# digitalLatchShieldSMD.net
KiCad netlist of a schematic drawn in EAGLE
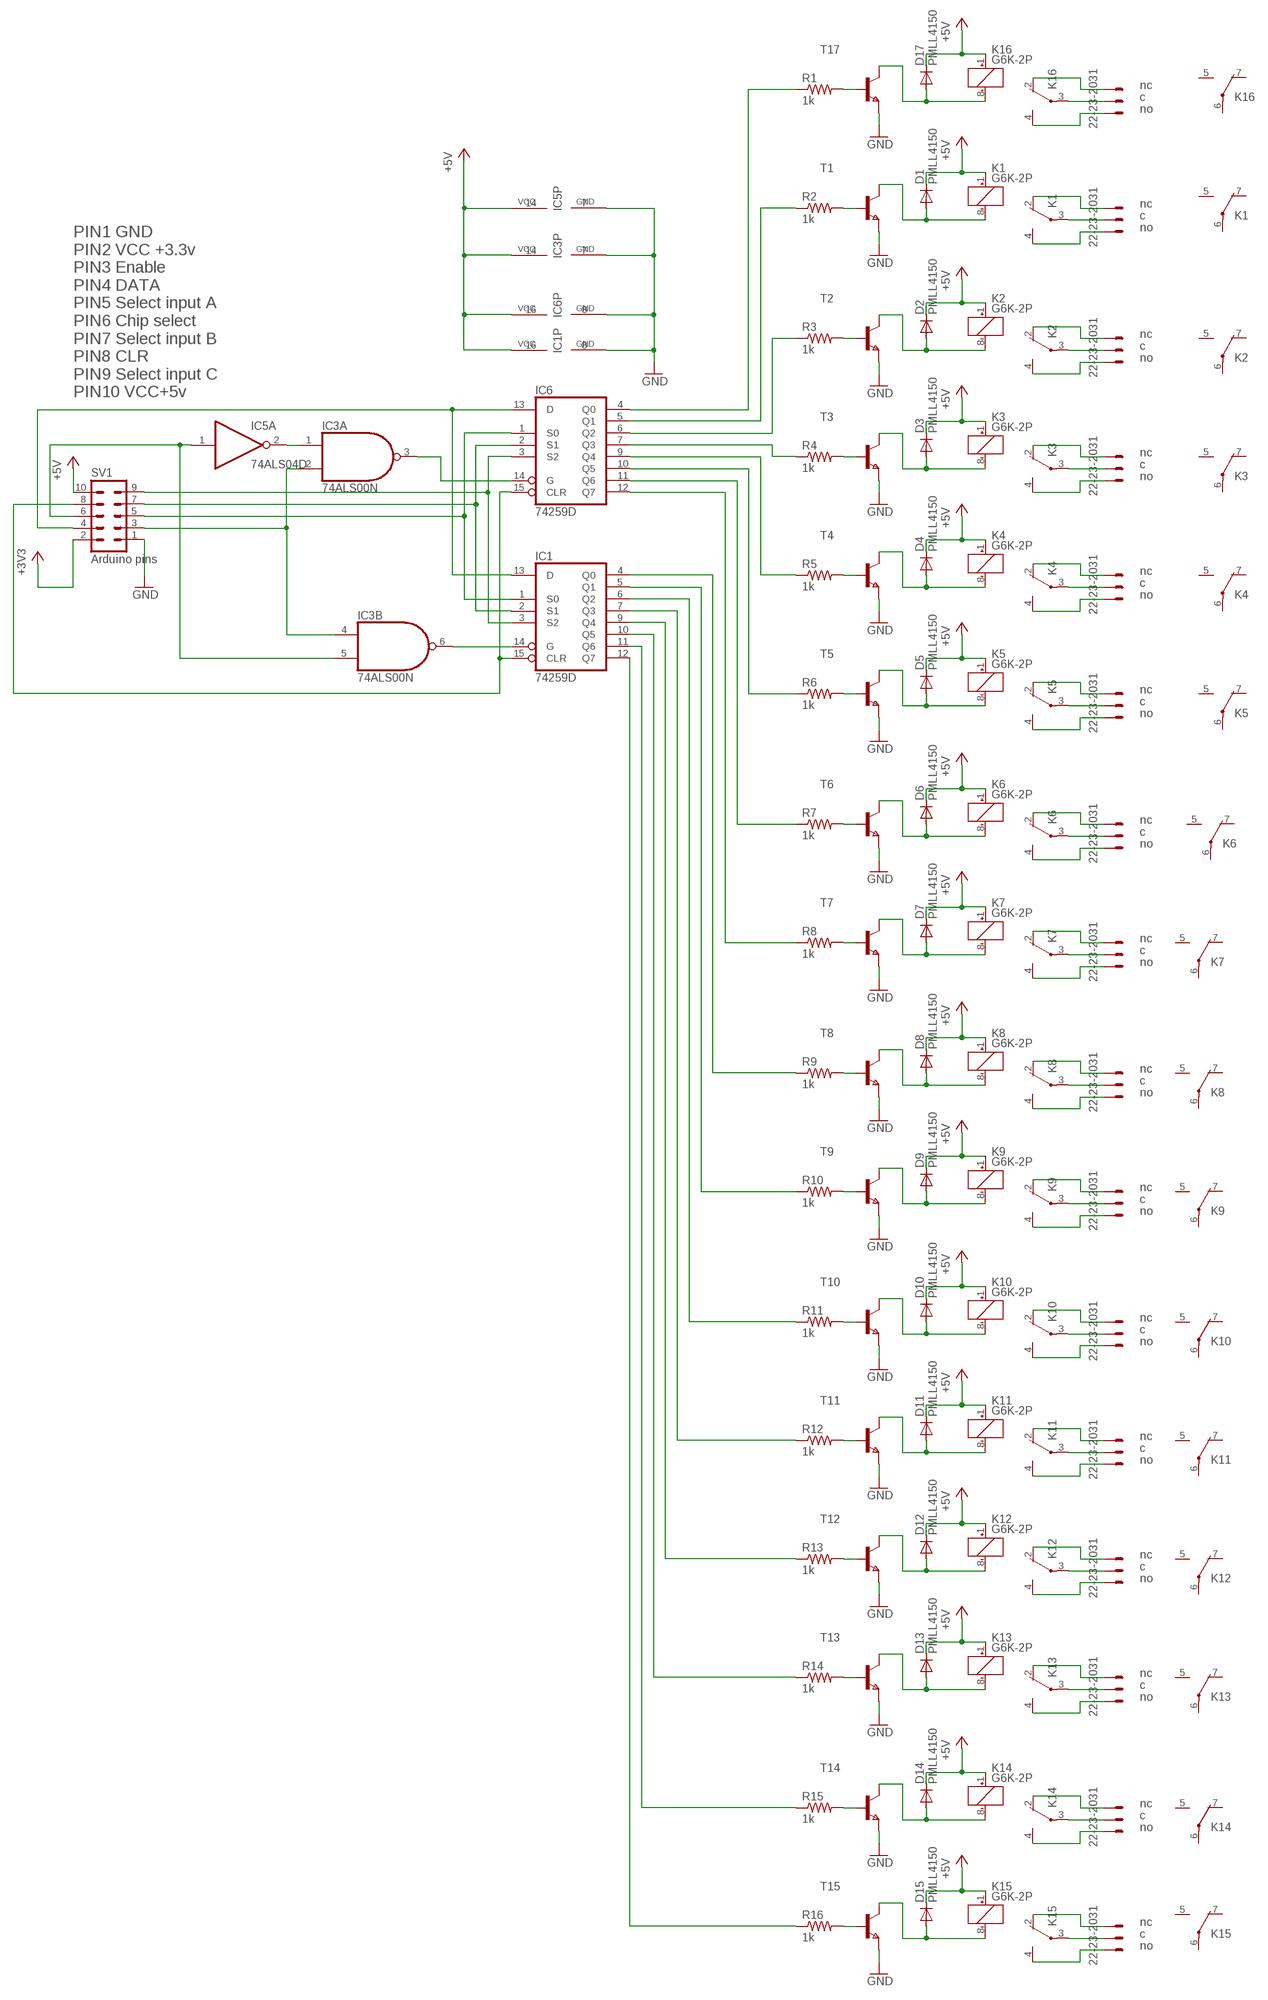
[diagram p0: schematic, sheet 1]

(export (version "E")
  (design (tool "Eeschema 10.0.6"))
  (components
    (comp (ref "D1")
      (value "PMLL4150")
      (footprint "eagle-import:SOD80C")
      (libsource (lib "eagle-import") (part "PMLL4150"))
    )
    (comp (ref "D2")
      (value "PMLL4150")
      (footprint "eagle-import:SOD80C")
      (libsource (lib "eagle-import") (part "PMLL4150"))
    )
    (comp (ref "D3")
      (value "PMLL4150")
      (footprint "eagle-import:SOD80C")
      (libsource (lib "eagle-import") (part "PMLL4150"))
    )
    (comp (ref "D4")
      (value "PMLL4150")
      (footprint "eagle-import:SOD80C")
      (libsource (lib "eagle-import") (part "PMLL4150"))
    )
    (comp (ref "D5")
      (value "PMLL4150")
      (footprint "eagle-import:SOD80C")
      (libsource (lib "eagle-import") (part "PMLL4150"))
    )
    (comp (ref "D6")
      (value "PMLL4150")
      (footprint "eagle-import:SOD80C")
      (libsource (lib "eagle-import") (part "PMLL4150"))
    )
    (comp (ref "D7")
      (value "PMLL4150")
      (footprint "eagle-import:SOD80C")
      (libsource (lib "eagle-import") (part "PMLL4150"))
    )
    (comp (ref "D8")
      (value "PMLL4150")
      (footprint "eagle-import:SOD80C")
      (libsource (lib "eagle-import") (part "PMLL4150"))
    )
    (comp (ref "D9")
      (value "PMLL4150")
      (footprint "eagle-import:SOD80C")
      (libsource (lib "eagle-import") (part "PMLL4150"))
    )
    (comp (ref "D10")
      (value "PMLL4150")
      (footprint "eagle-import:SOD80C")
      (libsource (lib "eagle-import") (part "PMLL4150"))
    )
    (comp (ref "D11")
      (value "PMLL4150")
      (footprint "eagle-import:SOD80C")
      (libsource (lib "eagle-import") (part "PMLL4150"))
    )
    (comp (ref "D12")
      (value "PMLL4150")
      (footprint "eagle-import:SOD80C")
      (libsource (lib "eagle-import") (part "PMLL4150"))
    )
    (comp (ref "D13")
      (value "PMLL4150")
      (footprint "eagle-import:SOD80C")
      (libsource (lib "eagle-import") (part "PMLL4150"))
    )
    (comp (ref "D14")
      (value "PMLL4150")
      (footprint "eagle-import:SOD80C")
      (libsource (lib "eagle-import") (part "PMLL4150"))
    )
    (comp (ref "D15")
      (value "PMLL4150")
      (footprint "eagle-import:SOD80C")
      (libsource (lib "eagle-import") (part "PMLL4150"))
    )
    (comp (ref "D17")
      (value "PMLL4150")
      (footprint "eagle-import:SOD80C")
      (libsource (lib "eagle-import") (part "PMLL4150"))
    )
    (comp (ref "IC1")
      (value "74259D")
      (footprint "eagle-import:SO16")
      (libsource (lib "eagle-import") (part "74259D"))
    )
    (comp (ref "IC3")
      (value "74ALS00N")
      (footprint "eagle-import:DIL14")
      (libsource (lib "eagle-import") (part "7400NALS"))
    )
    (comp (ref "IC5")
      (value "74ALS04D")
      (footprint "eagle-import:SO14")
      (libsource (lib "eagle-import") (part "7404DALS"))
    )
    (comp (ref "IC6")
      (value "74259D")
      (footprint "eagle-import:SO16")
      (libsource (lib "eagle-import") (part "74259D"))
    )
    (comp (ref "K1")
      (value "G6K-2P")
      (footprint "eagle-import:G6K-2P")
      (fields (field (name "MF") "OMRON COMPONENTS USA") (field (name "MPN") "G6K-2P DC3"))
      (libsource (lib "eagle-import") (part "G6K-2P"))
    )
    (comp (ref "K2")
      (value "G6K-2P")
      (footprint "eagle-import:G6K-2P")
      (fields (field (name "MF") "OMRON COMPONENTS USA") (field (name "MPN") "G6K-2P DC3"))
      (libsource (lib "eagle-import") (part "G6K-2P"))
    )
    (comp (ref "K3")
      (value "G6K-2P")
      (footprint "eagle-import:G6K-2P")
      (fields (field (name "MF") "OMRON COMPONENTS USA") (field (name "MPN") "G6K-2P DC3"))
      (libsource (lib "eagle-import") (part "G6K-2P"))
    )
    (comp (ref "K4")
      (value "G6K-2P")
      (footprint "eagle-import:G6K-2P")
      (fields (field (name "MF") "OMRON COMPONENTS USA") (field (name "MPN") "G6K-2P DC3"))
      (libsource (lib "eagle-import") (part "G6K-2P"))
    )
    (comp (ref "K5")
      (value "G6K-2P")
      (footprint "eagle-import:G6K-2P")
      (fields (field (name "MF") "OMRON COMPONENTS USA") (field (name "MPN") "G6K-2P DC3"))
      (libsource (lib "eagle-import") (part "G6K-2P"))
    )
    (comp (ref "K6")
      (value "G6K-2P")
      (footprint "eagle-import:G6K-2P")
      (fields (field (name "MF") "OMRON COMPONENTS USA") (field (name "MPN") "G6K-2P DC3"))
      (libsource (lib "eagle-import") (part "G6K-2P"))
    )
    (comp (ref "K7")
      (value "G6K-2P")
      (footprint "eagle-import:G6K-2P")
      (fields (field (name "MF") "OMRON COMPONENTS USA") (field (name "MPN") "G6K-2P DC3"))
      (libsource (lib "eagle-import") (part "G6K-2P"))
    )
    (comp (ref "K8")
      (value "G6K-2P")
      (footprint "eagle-import:G6K-2P")
      (fields (field (name "MF") "OMRON COMPONENTS USA") (field (name "MPN") "G6K-2P DC3"))
      (libsource (lib "eagle-import") (part "G6K-2P"))
    )
    (comp (ref "K9")
      (value "G6K-2P")
      (footprint "eagle-import:G6K-2P")
      (fields (field (name "MF") "OMRON COMPONENTS USA") (field (name "MPN") "G6K-2P DC3"))
      (libsource (lib "eagle-import") (part "G6K-2P"))
    )
    (comp (ref "K10")
      (value "G6K-2P")
      (footprint "eagle-import:G6K-2P")
      (fields (field (name "MF") "OMRON COMPONENTS USA") (field (name "MPN") "G6K-2P DC3"))
      (libsource (lib "eagle-import") (part "G6K-2P"))
    )
    (comp (ref "K11")
      (value "G6K-2P")
      (footprint "eagle-import:G6K-2P")
      (fields (field (name "MF") "OMRON COMPONENTS USA") (field (name "MPN") "G6K-2P DC3"))
      (libsource (lib "eagle-import") (part "G6K-2P"))
    )
    (comp (ref "K12")
      (value "G6K-2P")
      (footprint "eagle-import:G6K-2P")
      (fields (field (name "MF") "OMRON COMPONENTS USA") (field (name "MPN") "G6K-2P DC3"))
      (libsource (lib "eagle-import") (part "G6K-2P"))
    )
    (comp (ref "K13")
      (value "G6K-2P")
      (footprint "eagle-import:G6K-2P")
      (fields (field (name "MF") "OMRON COMPONENTS USA") (field (name "MPN") "G6K-2P DC3"))
      (libsource (lib "eagle-import") (part "G6K-2P"))
    )
    (comp (ref "K14")
      (value "G6K-2P")
      (footprint "eagle-import:G6K-2P")
      (fields (field (name "MF") "OMRON COMPONENTS USA") (field (name "MPN") "G6K-2P DC3"))
      (libsource (lib "eagle-import") (part "G6K-2P"))
    )
    (comp (ref "K15")
      (value "G6K-2P")
      (footprint "eagle-import:G6K-2P")
      (fields (field (name "MF") "OMRON COMPONENTS USA") (field (name "MPN") "G6K-2P DC3"))
      (libsource (lib "eagle-import") (part "G6K-2P"))
    )
    (comp (ref "K16")
      (value "G6K-2P")
      (footprint "eagle-import:G6K-2P")
      (fields (field (name "MF") "OMRON COMPONENTS USA") (field (name "MPN") "G6K-2P DC3"))
      (libsource (lib "eagle-import") (part "G6K-2P"))
    )
    (comp (ref "R1")
      (value "1k")
      (footprint "eagle-import:M0805")
      (libsource (lib "eagle-import") (part "R-US_M0805"))
    )
    (comp (ref "R2")
      (value "1k")
      (footprint "eagle-import:M0805")
      (libsource (lib "eagle-import") (part "R-US_M0805"))
    )
    (comp (ref "R3")
      (value "1k")
      (footprint "eagle-import:M0805")
      (libsource (lib "eagle-import") (part "R-US_M0805"))
    )
    (comp (ref "R4")
      (value "1k")
      (footprint "eagle-import:M0805")
      (libsource (lib "eagle-import") (part "R-US_M0805"))
    )
    (comp (ref "R5")
      (value "1k")
      (footprint "eagle-import:M0805")
      (libsource (lib "eagle-import") (part "R-US_M0805"))
    )
    (comp (ref "R6")
      (value "1k")
      (footprint "eagle-import:M0805")
      (libsource (lib "eagle-import") (part "R-US_M0805"))
    )
    (comp (ref "R7")
      (value "1k")
      (footprint "eagle-import:M0805")
      (libsource (lib "eagle-import") (part "R-US_M0805"))
    )
    (comp (ref "R8")
      (value "1k")
      (footprint "eagle-import:M0805")
      (libsource (lib "eagle-import") (part "R-US_M0805"))
    )
    (comp (ref "R9")
      (value "1k")
      (footprint "eagle-import:M0805")
      (libsource (lib "eagle-import") (part "R-US_M0805"))
    )
    (comp (ref "R10")
      (value "1k")
      (footprint "eagle-import:M0805")
      (libsource (lib "eagle-import") (part "R-US_M0805"))
    )
    (comp (ref "R11")
      (value "1k")
      (footprint "eagle-import:M0805")
      (libsource (lib "eagle-import") (part "R-US_M0805"))
    )
    (comp (ref "R12")
      (value "1k")
      (footprint "eagle-import:M0805")
      (libsource (lib "eagle-import") (part "R-US_M0805"))
    )
    (comp (ref "R13")
      (value "1k")
      (footprint "eagle-import:M0805")
      (libsource (lib "eagle-import") (part "R-US_M0805"))
    )
    (comp (ref "R14")
      (value "1k")
      (footprint "eagle-import:M0805")
      (libsource (lib "eagle-import") (part "R-US_M0805"))
    )
    (comp (ref "R15")
      (value "1k")
      (footprint "eagle-import:M0805")
      (libsource (lib "eagle-import") (part "R-US_M0805"))
    )
    (comp (ref "R16")
      (value "1k")
      (footprint "eagle-import:M0805")
      (libsource (lib "eagle-import") (part "R-US_M0805"))
    )
    (comp (ref "SV1")
      (value "Arduino pins")
      (footprint "eagle-import:MA05-2")
      (libsource (lib "eagle-import") (part "MA05-2"))
    )
    (comp (ref "T1")
      (value "NPNSOT23")
      (footprint "eagle-import:SOT-23")
      (fields (field (name "MPN") "DSS20201L-7"))
      (libsource (lib "eagle-import") (part "NPNSOT23"))
    )
    (comp (ref "T2")
      (value "NPNSOT23")
      (footprint "eagle-import:SOT-23")
      (fields (field (name "MPN") "DSS20201L-7"))
      (libsource (lib "eagle-import") (part "NPNSOT23"))
    )
    (comp (ref "T3")
      (value "NPNSOT23")
      (footprint "eagle-import:SOT-23")
      (fields (field (name "MPN") "DSS20201L-7"))
      (libsource (lib "eagle-import") (part "NPNSOT23"))
    )
    (comp (ref "T4")
      (value "NPNSOT23")
      (footprint "eagle-import:SOT-23")
      (fields (field (name "MPN") "DSS20201L-7"))
      (libsource (lib "eagle-import") (part "NPNSOT23"))
    )
    (comp (ref "T5")
      (value "NPNSOT23")
      (footprint "eagle-import:SOT-23")
      (fields (field (name "MPN") "DSS20201L-7"))
      (libsource (lib "eagle-import") (part "NPNSOT23"))
    )
    (comp (ref "T6")
      (value "NPNSOT23")
      (footprint "eagle-import:SOT-23")
      (fields (field (name "MPN") "DSS20201L-7"))
      (libsource (lib "eagle-import") (part "NPNSOT23"))
    )
    (comp (ref "T7")
      (value "NPNSOT23")
      (footprint "eagle-import:SOT-23")
      (fields (field (name "MPN") "DSS20201L-7"))
      (libsource (lib "eagle-import") (part "NPNSOT23"))
    )
    (comp (ref "T8")
      (value "NPNSOT23")
      (footprint "eagle-import:SOT-23")
      (fields (field (name "MPN") "DSS20201L-7"))
      (libsource (lib "eagle-import") (part "NPNSOT23"))
    )
    (comp (ref "T9")
      (value "NPNSOT23")
      (footprint "eagle-import:SOT-23")
      (fields (field (name "MPN") "DSS20201L-7"))
      (libsource (lib "eagle-import") (part "NPNSOT23"))
    )
    (comp (ref "T10")
      (value "NPNSOT23")
      (footprint "eagle-import:SOT-23")
      (fields (field (name "MPN") "DSS20201L-7"))
      (libsource (lib "eagle-import") (part "NPNSOT23"))
    )
    (comp (ref "T11")
      (value "NPNSOT23")
      (footprint "eagle-import:SOT-23")
      (fields (field (name "MPN") "DSS20201L-7"))
      (libsource (lib "eagle-import") (part "NPNSOT23"))
    )
    (comp (ref "T12")
      (value "NPNSOT23")
      (footprint "eagle-import:SOT-23")
      (fields (field (name "MPN") "DSS20201L-7"))
      (libsource (lib "eagle-import") (part "NPNSOT23"))
    )
    (comp (ref "T13")
      (value "NPNSOT23")
      (footprint "eagle-import:SOT-23")
      (fields (field (name "MPN") "DSS20201L-7"))
      (libsource (lib "eagle-import") (part "NPNSOT23"))
    )
    (comp (ref "T14")
      (value "NPNSOT23")
      (footprint "eagle-import:SOT-23")
      (fields (field (name "MPN") "DSS20201L-7"))
      (libsource (lib "eagle-import") (part "NPNSOT23"))
    )
    (comp (ref "T15")
      (value "NPNSOT23")
      (footprint "eagle-import:SOT-23")
      (fields (field (name "MPN") "DSS20201L-7"))
      (libsource (lib "eagle-import") (part "NPNSOT23"))
    )
    (comp (ref "T17")
      (value "NPNSOT23")
      (footprint "eagle-import:SOT-23")
      (fields (field (name "MPN") "DSS20201L-7"))
      (libsource (lib "eagle-import") (part "NPNSOT23"))
    )
    (comp (ref "X1")
      (value "22-23-2031")
      (footprint "eagle-import:22-23-2031")
      (fields (field (name "MF") "MOLEX"))
      (libsource (lib "eagle-import") (part "22-23-2031"))
    )
    (comp (ref "X2")
      (value "22-23-2031")
      (footprint "eagle-import:22-23-2031")
      (fields (field (name "MF") "MOLEX"))
      (libsource (lib "eagle-import") (part "22-23-2031"))
    )
    (comp (ref "X3")
      (value "22-23-2031")
      (footprint "eagle-import:22-23-2031")
      (fields (field (name "MF") "MOLEX"))
      (libsource (lib "eagle-import") (part "22-23-2031"))
    )
    (comp (ref "X4")
      (value "22-23-2031")
      (footprint "eagle-import:22-23-2031")
      (fields (field (name "MF") "MOLEX"))
      (libsource (lib "eagle-import") (part "22-23-2031"))
    )
    (comp (ref "X5")
      (value "22-23-2031")
      (footprint "eagle-import:22-23-2031")
      (fields (field (name "MF") "MOLEX"))
      (libsource (lib "eagle-import") (part "22-23-2031"))
    )
    (comp (ref "X6")
      (value "22-23-2031")
      (footprint "eagle-import:22-23-2031")
      (fields (field (name "MF") "MOLEX"))
      (libsource (lib "eagle-import") (part "22-23-2031"))
    )
    (comp (ref "X7")
      (value "22-23-2031")
      (footprint "eagle-import:22-23-2031")
      (fields (field (name "MF") "MOLEX"))
      (libsource (lib "eagle-import") (part "22-23-2031"))
    )
    (comp (ref "X8")
      (value "22-23-2031")
      (footprint "eagle-import:22-23-2031")
      (fields (field (name "MF") "MOLEX"))
      (libsource (lib "eagle-import") (part "22-23-2031"))
    )
    (comp (ref "X9")
      (value "22-23-2031")
      (footprint "eagle-import:22-23-2031")
      (fields (field (name "MF") "MOLEX"))
      (libsource (lib "eagle-import") (part "22-23-2031"))
    )
    (comp (ref "X10")
      (value "22-23-2031")
      (footprint "eagle-import:22-23-2031")
      (fields (field (name "MF") "MOLEX"))
      (libsource (lib "eagle-import") (part "22-23-2031"))
    )
    (comp (ref "X11")
      (value "22-23-2031")
      (footprint "eagle-import:22-23-2031")
      (fields (field (name "MF") "MOLEX"))
      (libsource (lib "eagle-import") (part "22-23-2031"))
    )
    (comp (ref "X12")
      (value "22-23-2031")
      (footprint "eagle-import:22-23-2031")
      (fields (field (name "MF") "MOLEX"))
      (libsource (lib "eagle-import") (part "22-23-2031"))
    )
    (comp (ref "X13")
      (value "22-23-2031")
      (footprint "eagle-import:22-23-2031")
      (fields (field (name "MF") "MOLEX"))
      (libsource (lib "eagle-import") (part "22-23-2031"))
    )
    (comp (ref "X14")
      (value "22-23-2031")
      (footprint "eagle-import:22-23-2031")
      (fields (field (name "MF") "MOLEX"))
      (libsource (lib "eagle-import") (part "22-23-2031"))
    )
    (comp (ref "X15")
      (value "22-23-2031")
      (footprint "eagle-import:22-23-2031")
      (fields (field (name "MF") "MOLEX"))
      (libsource (lib "eagle-import") (part "22-23-2031"))
    )
    (comp (ref "X16")
      (value "22-23-2031")
      (footprint "eagle-import:22-23-2031")
      (fields (field (name "MF") "MOLEX"))
      (libsource (lib "eagle-import") (part "22-23-2031"))
    )
  )
  (nets
    (net (code "1") (name "+3V3") (class "Default")
      (node (ref "SV1") (pin "2") (pinfunction "2_2") (pintype "passive"))
    )
    (net (code "2") (name "+5V") (class "Default")
      (node (ref "D1") (pin "C") (pinfunction "C_C") (pintype "passive"))
      (node (ref "D10") (pin "C") (pinfunction "C_C") (pintype "passive"))
      (node (ref "D11") (pin "C") (pinfunction "C_C") (pintype "passive"))
      (node (ref "D12") (pin "C") (pinfunction "C_C") (pintype "passive"))
      (node (ref "D13") (pin "C") (pinfunction "C_C") (pintype "passive"))
      (node (ref "D14") (pin "C") (pinfunction "C_C") (pintype "passive"))
      (node (ref "D15") (pin "C") (pinfunction "C_C") (pintype "passive"))
      (node (ref "D17") (pin "C") (pinfunction "C_C") (pintype "passive"))
      (node (ref "D2") (pin "C") (pinfunction "C_C") (pintype "passive"))
      (node (ref "D3") (pin "C") (pinfunction "C_C") (pintype "passive"))
      (node (ref "D4") (pin "C") (pinfunction "C_C") (pintype "passive"))
      (node (ref "D5") (pin "C") (pinfunction "C_C") (pintype "passive"))
      (node (ref "D6") (pin "C") (pinfunction "C_C") (pintype "passive"))
      (node (ref "D7") (pin "C") (pinfunction "C_C") (pintype "passive"))
      (node (ref "D8") (pin "C") (pinfunction "C_C") (pintype "passive"))
      (node (ref "D9") (pin "C") (pinfunction "C_C") (pintype "passive"))
      (node (ref "IC1") (pin "16") (pinfunction "VCC_16") (pintype "power_in"))
      (node (ref "IC3") (pin "14") (pinfunction "VCC_14") (pintype "power_in"))
      (node (ref "IC5") (pin "14") (pinfunction "VCC_14") (pintype "power_in"))
      (node (ref "IC6") (pin "16") (pinfunction "VCC_16") (pintype "power_in"))
      (node (ref "K1") (pin "1") (pinfunction "+_1") (pintype "passive"))
      (node (ref "K10") (pin "1") (pinfunction "+_1") (pintype "passive"))
      (node (ref "K11") (pin "1") (pinfunction "+_1") (pintype "passive"))
      (node (ref "K12") (pin "1") (pinfunction "+_1") (pintype "passive"))
      (node (ref "K13") (pin "1") (pinfunction "+_1") (pintype "passive"))
      (node (ref "K14") (pin "1") (pinfunction "+_1") (pintype "passive"))
      (node (ref "K15") (pin "1") (pinfunction "+_1") (pintype "passive"))
      (node (ref "K16") (pin "1") (pinfunction "+_1") (pintype "passive"))
      (node (ref "K2") (pin "1") (pinfunction "+_1") (pintype "passive"))
      (node (ref "K3") (pin "1") (pinfunction "+_1") (pintype "passive"))
      (node (ref "K4") (pin "1") (pinfunction "+_1") (pintype "passive"))
      (node (ref "K5") (pin "1") (pinfunction "+_1") (pintype "passive"))
      (node (ref "K6") (pin "1") (pinfunction "+_1") (pintype "passive"))
      (node (ref "K7") (pin "1") (pinfunction "+_1") (pintype "passive"))
      (node (ref "K8") (pin "1") (pinfunction "+_1") (pintype "passive"))
      (node (ref "K9") (pin "1") (pinfunction "+_1") (pintype "passive"))
      (node (ref "SV1") (pin "10") (pinfunction "10_10") (pintype "passive"))
    )
    (net (code "3") (name "GND") (class "Default")
      (node (ref "IC1") (pin "8") (pinfunction "GND_8") (pintype "power_in"))
      (node (ref "IC3") (pin "7") (pinfunction "GND_7") (pintype "power_in"))
      (node (ref "IC5") (pin "7") (pinfunction "GND_7") (pintype "power_in"))
      (node (ref "IC6") (pin "8") (pinfunction "GND_8") (pintype "power_in"))
      (node (ref "SV1") (pin "1") (pinfunction "1_1") (pintype "passive"))
      (node (ref "T1") (pin "2") (pinfunction "E_2") (pintype "passive"))
      (node (ref "T10") (pin "2") (pinfunction "E_2") (pintype "passive"))
      (node (ref "T11") (pin "2") (pinfunction "E_2") (pintype "passive"))
      (node (ref "T12") (pin "2") (pinfunction "E_2") (pintype "passive"))
      (node (ref "T13") (pin "2") (pinfunction "E_2") (pintype "passive"))
      (node (ref "T14") (pin "2") (pinfunction "E_2") (pintype "passive"))
      (node (ref "T15") (pin "2") (pinfunction "E_2") (pintype "passive"))
      (node (ref "T17") (pin "2") (pinfunction "E_2") (pintype "passive"))
      (node (ref "T2") (pin "2") (pinfunction "E_2") (pintype "passive"))
      (node (ref "T3") (pin "2") (pinfunction "E_2") (pintype "passive"))
      (node (ref "T4") (pin "2") (pinfunction "E_2") (pintype "passive"))
      (node (ref "T5") (pin "2") (pinfunction "E_2") (pintype "passive"))
      (node (ref "T6") (pin "2") (pinfunction "E_2") (pintype "passive"))
      (node (ref "T7") (pin "2") (pinfunction "E_2") (pintype "passive"))
      (node (ref "T8") (pin "2") (pinfunction "E_2") (pintype "passive"))
      (node (ref "T9") (pin "2") (pinfunction "E_2") (pintype "passive"))
    )
    (net (code "4") (name "Net-(IC1A-CLR)") (class "Default")
      (node (ref "IC1") (pin "15") (pinfunction "CLR_15") (pintype "input"))
      (node (ref "IC6") (pin "15") (pinfunction "CLR_15") (pintype "input"))
      (node (ref "SV1") (pin "8") (pinfunction "8_8") (pintype "passive"))
    )
    (net (code "5") (name "Net-(IC1A-D)") (class "Default")
      (node (ref "IC1") (pin "13") (pinfunction "D_13") (pintype "input"))
      (node (ref "IC6") (pin "13") (pinfunction "D_13") (pintype "input"))
      (node (ref "SV1") (pin "4") (pinfunction "4_4") (pintype "passive"))
    )
    (net (code "6") (name "Net-(IC1A-G)") (class "Default")
      (node (ref "IC1") (pin "14") (pinfunction "G_14") (pintype "input"))
      (node (ref "IC3") (pin "6") (pinfunction "O_6") (pintype "output"))
    )
    (net (code "7") (name "Net-(IC1A-Q0)") (class "Default")
      (node (ref "IC1") (pin "4") (pinfunction "Q0_4") (pintype "output"))
      (node (ref "R9") (pin "1") (pinfunction "1_1") (pintype "passive"))
    )
    (net (code "8") (name "Net-(IC1A-Q1)") (class "Default")
      (node (ref "IC1") (pin "5") (pinfunction "Q1_5") (pintype "output"))
      (node (ref "R10") (pin "1") (pinfunction "1_1") (pintype "passive"))
    )
    (net (code "9") (name "Net-(IC1A-Q2)") (class "Default")
      (node (ref "IC1") (pin "6") (pinfunction "Q2_6") (pintype "output"))
      (node (ref "R11") (pin "1") (pinfunction "1_1") (pintype "passive"))
    )
    (net (code "10") (name "Net-(IC1A-Q3)") (class "Default")
      (node (ref "IC1") (pin "7") (pinfunction "Q3_7") (pintype "output"))
      (node (ref "R12") (pin "1") (pinfunction "1_1") (pintype "passive"))
    )
    (net (code "11") (name "Net-(IC1A-Q4)") (class "Default")
      (node (ref "IC1") (pin "9") (pinfunction "Q4_9") (pintype "output"))
      (node (ref "R13") (pin "1") (pinfunction "1_1") (pintype "passive"))
    )
    (net (code "12") (name "Net-(IC1A-Q5)") (class "Default")
      (node (ref "IC1") (pin "10") (pinfunction "Q5_10") (pintype "output"))
      (node (ref "R14") (pin "1") (pinfunction "1_1") (pintype "passive"))
    )
    (net (code "13") (name "Net-(IC1A-Q6)") (class "Default")
      (node (ref "IC1") (pin "11") (pinfunction "Q6_11") (pintype "output"))
      (node (ref "R15") (pin "1") (pinfunction "1_1") (pintype "passive"))
    )
    (net (code "14") (name "Net-(IC1A-Q7)") (class "Default")
      (node (ref "IC1") (pin "12") (pinfunction "Q7_12") (pintype "output"))
      (node (ref "R16") (pin "1") (pinfunction "1_1") (pintype "passive"))
    )
    (net (code "15") (name "Net-(IC1A-S0)") (class "Default")
      (node (ref "IC1") (pin "1") (pinfunction "S0_1") (pintype "input"))
      (node (ref "IC6") (pin "1") (pinfunction "S0_1") (pintype "input"))
      (node (ref "SV1") (pin "5") (pinfunction "5_5") (pintype "passive"))
    )
    (net (code "16") (name "Net-(IC1A-S1)") (class "Default")
      (node (ref "IC1") (pin "2") (pinfunction "S1_2") (pintype "input"))
      (node (ref "IC6") (pin "2") (pinfunction "S1_2") (pintype "input"))
      (node (ref "SV1") (pin "7") (pinfunction "7_7") (pintype "passive"))
    )
    (net (code "17") (name "Net-(IC1A-S2)") (class "Default")
      (node (ref "IC1") (pin "3") (pinfunction "S2_3") (pintype "input"))
      (node (ref "IC6") (pin "3") (pinfunction "S2_3") (pintype "input"))
      (node (ref "SV1") (pin "9") (pinfunction "9_9") (pintype "passive"))
    )
    (net (code "18") (name "Net-(IC3A-I0)") (class "Default")
      (node (ref "IC3") (pin "1") (pinfunction "I0_1") (pintype "input"))
      (node (ref "IC5") (pin "2") (pinfunction "O_2") (pintype "output"))
    )
    (net (code "19") (name "Net-(IC3A-I1)") (class "Default")
      (node (ref "IC3") (pin "2") (pinfunction "I1_2") (pintype "input"))
      (node (ref "IC3") (pin "4") (pinfunction "I0_4") (pintype "input"))
      (node (ref "SV1") (pin "3") (pinfunction "3_3") (pintype "passive"))
    )
    (net (code "20") (name "Net-(IC3A-O)") (class "Default")
      (node (ref "IC3") (pin "3") (pinfunction "O_3") (pintype "output"))
      (node (ref "IC6") (pin "14") (pinfunction "G_14") (pintype "input"))
    )
    (net (code "21") (name "Net-(IC3B-I1)") (class "Default")
      (node (ref "IC3") (pin "5") (pinfunction "I1_5") (pintype "input"))
      (node (ref "IC5") (pin "1") (pinfunction "I_1") (pintype "input"))
      (node (ref "SV1") (pin "6") (pinfunction "6_6") (pintype "passive"))
    )
    (net (code "22") (name "Net-(IC6A-Q0)") (class "Default")
      (node (ref "IC6") (pin "4") (pinfunction "Q0_4") (pintype "output"))
      (node (ref "R1") (pin "1") (pinfunction "1_1") (pintype "passive"))
    )
    (net (code "23") (name "Net-(IC6A-Q1)") (class "Default")
      (node (ref "IC6") (pin "5") (pinfunction "Q1_5") (pintype "output"))
      (node (ref "R2") (pin "1") (pinfunction "1_1") (pintype "passive"))
    )
    (net (code "24") (name "Net-(IC6A-Q2)") (class "Default")
      (node (ref "IC6") (pin "6") (pinfunction "Q2_6") (pintype "output"))
      (node (ref "R3") (pin "1") (pinfunction "1_1") (pintype "passive"))
    )
    (net (code "25") (name "Net-(IC6A-Q3)") (class "Default")
      (node (ref "IC6") (pin "7") (pinfunction "Q3_7") (pintype "output"))
      (node (ref "R4") (pin "1") (pinfunction "1_1") (pintype "passive"))
    )
    (net (code "26") (name "Net-(IC6A-Q4)") (class "Default")
      (node (ref "IC6") (pin "9") (pinfunction "Q4_9") (pintype "output"))
      (node (ref "R5") (pin "1") (pinfunction "1_1") (pintype "passive"))
    )
    (net (code "27") (name "Net-(IC6A-Q5)") (class "Default")
      (node (ref "IC6") (pin "10") (pinfunction "Q5_10") (pintype "output"))
      (node (ref "R6") (pin "1") (pinfunction "1_1") (pintype "passive"))
    )
    (net (code "28") (name "Net-(IC6A-Q6)") (class "Default")
      (node (ref "IC6") (pin "11") (pinfunction "Q6_11") (pintype "output"))
      (node (ref "R7") (pin "1") (pinfunction "1_1") (pintype "passive"))
    )
    (net (code "29") (name "Net-(IC6A-Q7)") (class "Default")
      (node (ref "IC6") (pin "12") (pinfunction "Q7_12") (pintype "output"))
      (node (ref "R8") (pin "1") (pinfunction "1_1") (pintype "passive"))
    )
    (net (code "30") (name "Net-(K1A--)") (class "Default")
      (node (ref "D1") (pin "A") (pinfunction "A_A") (pintype "passive"))
      (node (ref "K1") (pin "8") (pinfunction "-_8") (pintype "passive"))
      (node (ref "T1") (pin "1") (pinfunction "C_1") (pintype "passive"))
    )
    (net (code "31") (name "Net-(K1B-O)") (class "Default")
      (node (ref "K1") (pin "2") (pinfunction "O_2") (pintype "passive"))
      (node (ref "X2") (pin "1") (pinfunction "S_1") (pintype "passive"))
    )
    (net (code "32") (name "Net-(K1B-P)") (class "Default")
      (node (ref "K1") (pin "3") (pinfunction "P_3") (pintype "passive"))
      (node (ref "X2") (pin "2") (pinfunction "S_2") (pintype "passive"))
    )
    (net (code "33") (name "Net-(K1B-S)") (class "Default")
      (node (ref "K1") (pin "4") (pinfunction "S_4") (pintype "passive"))
      (node (ref "X2") (pin "3") (pinfunction "S_3") (pintype "passive"))
    )
    (net (code "34") (name "Net-(K2A--)") (class "Default")
      (node (ref "D2") (pin "A") (pinfunction "A_A") (pintype "passive"))
      (node (ref "K2") (pin "8") (pinfunction "-_8") (pintype "passive"))
      (node (ref "T2") (pin "1") (pinfunction "C_1") (pintype "passive"))
    )
    (net (code "35") (name "Net-(K2B-O)") (class "Default")
      (node (ref "K2") (pin "2") (pinfunction "O_2") (pintype "passive"))
      (node (ref "X3") (pin "1") (pinfunction "S_1") (pintype "passive"))
    )
    (net (code "36") (name "Net-(K2B-P)") (class "Default")
      (node (ref "K2") (pin "3") (pinfunction "P_3") (pintype "passive"))
      (node (ref "X3") (pin "2") (pinfunction "S_2") (pintype "passive"))
    )
    (net (code "37") (name "Net-(K2B-S)") (class "Default")
      (node (ref "K2") (pin "4") (pinfunction "S_4") (pintype "passive"))
      (node (ref "X3") (pin "3") (pinfunction "S_3") (pintype "passive"))
    )
    (net (code "38") (name "Net-(K3A--)") (class "Default")
      (node (ref "D3") (pin "A") (pinfunction "A_A") (pintype "passive"))
      (node (ref "K3") (pin "8") (pinfunction "-_8") (pintype "passive"))
      (node (ref "T3") (pin "1") (pinfunction "C_1") (pintype "passive"))
    )
    (net (code "39") (name "Net-(K3B-O)") (class "Default")
      (node (ref "K3") (pin "2") (pinfunction "O_2") (pintype "passive"))
      (node (ref "X4") (pin "1") (pinfunction "S_1") (pintype "passive"))
    )
    (net (code "40") (name "Net-(K3B-P)") (class "Default")
      (node (ref "K3") (pin "3") (pinfunction "P_3") (pintype "passive"))
      (node (ref "X4") (pin "2") (pinfunction "S_2") (pintype "passive"))
    )
    (net (code "41") (name "Net-(K3B-S)") (class "Default")
      (node (ref "K3") (pin "4") (pinfunction "S_4") (pintype "passive"))
      (node (ref "X4") (pin "3") (pinfunction "S_3") (pintype "passive"))
    )
    (net (code "42") (name "Net-(K4A--)") (class "Default")
      (node (ref "D4") (pin "A") (pinfunction "A_A") (pintype "passive"))
      (node (ref "K4") (pin "8") (pinfunction "-_8") (pintype "passive"))
      (node (ref "T4") (pin "1") (pinfunction "C_1") (pintype "passive"))
    )
    (net (code "43") (name "Net-(K4B-O)") (class "Default")
      (node (ref "K4") (pin "2") (pinfunction "O_2") (pintype "passive"))
      (node (ref "X5") (pin "1") (pinfunction "S_1") (pintype "passive"))
    )
    (net (code "44") (name "Net-(K4B-P)") (class "Default")
      (node (ref "K4") (pin "3") (pinfunction "P_3") (pintype "passive"))
      (node (ref "X5") (pin "2") (pinfunction "S_2") (pintype "passive"))
    )
    (net (code "45") (name "Net-(K4B-S)") (class "Default")
      (node (ref "K4") (pin "4") (pinfunction "S_4") (pintype "passive"))
      (node (ref "X5") (pin "3") (pinfunction "S_3") (pintype "passive"))
    )
    (net (code "46") (name "Net-(K5A--)") (class "Default")
      (node (ref "D5") (pin "A") (pinfunction "A_A") (pintype "passive"))
      (node (ref "K5") (pin "8") (pinfunction "-_8") (pintype "passive"))
      (node (ref "T5") (pin "1") (pinfunction "C_1") (pintype "passive"))
    )
    (net (code "47") (name "Net-(K5B-O)") (class "Default")
      (node (ref "K5") (pin "2") (pinfunction "O_2") (pintype "passive"))
      (node (ref "X6") (pin "1") (pinfunction "S_1") (pintype "passive"))
    )
    (net (code "48") (name "Net-(K5B-P)") (class "Default")
      (node (ref "K5") (pin "3") (pinfunction "P_3") (pintype "passive"))
      (node (ref "X6") (pin "2") (pinfunction "S_2") (pintype "passive"))
    )
    (net (code "49") (name "Net-(K5B-S)") (class "Default")
      (node (ref "K5") (pin "4") (pinfunction "S_4") (pintype "passive"))
      (node (ref "X6") (pin "3") (pinfunction "S_3") (pintype "passive"))
    )
    (net (code "50") (name "Net-(K6A--)") (class "Default")
      (node (ref "D6") (pin "A") (pinfunction "A_A") (pintype "passive"))
      (node (ref "K6") (pin "8") (pinfunction "-_8") (pintype "passive"))
      (node (ref "T6") (pin "1") (pinfunction "C_1") (pintype "passive"))
    )
    (net (code "51") (name "Net-(K6B-O)") (class "Default")
      (node (ref "K6") (pin "2") (pinfunction "O_2") (pintype "passive"))
      (node (ref "X7") (pin "1") (pinfunction "S_1") (pintype "passive"))
    )
    (net (code "52") (name "Net-(K6B-P)") (class "Default")
      (node (ref "K6") (pin "3") (pinfunction "P_3") (pintype "passive"))
      (node (ref "X7") (pin "2") (pinfunction "S_2") (pintype "passive"))
    )
    (net (code "53") (name "Net-(K6B-S)") (class "Default")
      (node (ref "K6") (pin "4") (pinfunction "S_4") (pintype "passive"))
      (node (ref "X7") (pin "3") (pinfunction "S_3") (pintype "passive"))
    )
    (net (code "54") (name "Net-(K7A--)") (class "Default")
      (node (ref "D7") (pin "A") (pinfunction "A_A") (pintype "passive"))
      (node (ref "K7") (pin "8") (pinfunction "-_8") (pintype "passive"))
      (node (ref "T7") (pin "1") (pinfunction "C_1") (pintype "passive"))
    )
    (net (code "55") (name "Net-(K7B-O)") (class "Default")
      (node (ref "K7") (pin "2") (pinfunction "O_2") (pintype "passive"))
      (node (ref "X8") (pin "1") (pinfunction "S_1") (pintype "passive"))
    )
    (net (code "56") (name "Net-(K7B-P)") (class "Default")
      (node (ref "K7") (pin "3") (pinfunction "P_3") (pintype "passive"))
      (node (ref "X8") (pin "2") (pinfunction "S_2") (pintype "passive"))
    )
    (net (code "57") (name "Net-(K7B-S)") (class "Default")
      (node (ref "K7") (pin "4") (pinfunction "S_4") (pintype "passive"))
      (node (ref "X8") (pin "3") (pinfunction "S_3") (pintype "passive"))
    )
    (net (code "58") (name "Net-(K8A--)") (class "Default")
      (node (ref "D8") (pin "A") (pinfunction "A_A") (pintype "passive"))
      (node (ref "K8") (pin "8") (pinfunction "-_8") (pintype "passive"))
      (node (ref "T8") (pin "1") (pinfunction "C_1") (pintype "passive"))
    )
    (net (code "59") (name "Net-(K8B-O)") (class "Default")
      (node (ref "K8") (pin "2") (pinfunction "O_2") (pintype "passive"))
      (node (ref "X9") (pin "1") (pinfunction "S_1") (pintype "passive"))
    )
    (net (code "60") (name "Net-(K8B-P)") (class "Default")
      (node (ref "K8") (pin "3") (pinfunction "P_3") (pintype "passive"))
      (node (ref "X9") (pin "2") (pinfunction "S_2") (pintype "passive"))
    )
    (net (code "61") (name "Net-(K8B-S)") (class "Default")
      (node (ref "K8") (pin "4") (pinfunction "S_4") (pintype "passive"))
      (node (ref "X9") (pin "3") (pinfunction "S_3") (pintype "passive"))
    )
    (net (code "62") (name "Net-(K9A--)") (class "Default")
      (node (ref "D9") (pin "A") (pinfunction "A_A") (pintype "passive"))
      (node (ref "K9") (pin "8") (pinfunction "-_8") (pintype "passive"))
      (node (ref "T9") (pin "1") (pinfunction "C_1") (pintype "passive"))
    )
    (net (code "63") (name "Net-(K9B-O)") (class "Default")
      (node (ref "K9") (pin "2") (pinfunction "O_2") (pintype "passive"))
      (node (ref "X10") (pin "1") (pinfunction "S_1") (pintype "passive"))
    )
    (net (code "64") (name "Net-(K9B-P)") (class "Default")
      (node (ref "K9") (pin "3") (pinfunction "P_3") (pintype "passive"))
      (node (ref "X10") (pin "2") (pinfunction "S_2") (pintype "passive"))
    )
    (net (code "65") (name "Net-(K9B-S)") (class "Default")
      (node (ref "K9") (pin "4") (pinfunction "S_4") (pintype "passive"))
      (node (ref "X10") (pin "3") (pinfunction "S_3") (pintype "passive"))
    )
    (net (code "66") (name "Net-(K10A--)") (class "Default")
      (node (ref "D10") (pin "A") (pinfunction "A_A") (pintype "passive"))
      (node (ref "K10") (pin "8") (pinfunction "-_8") (pintype "passive"))
      (node (ref "T10") (pin "1") (pinfunction "C_1") (pintype "passive"))
    )
    (net (code "67") (name "Net-(K10B-O)") (class "Default")
      (node (ref "K10") (pin "2") (pinfunction "O_2") (pintype "passive"))
      (node (ref "X11") (pin "1") (pinfunction "S_1") (pintype "passive"))
    )
    (net (code "68") (name "Net-(K10B-P)") (class "Default")
      (node (ref "K10") (pin "3") (pinfunction "P_3") (pintype "passive"))
      (node (ref "X11") (pin "2") (pinfunction "S_2") (pintype "passive"))
    )
    (net (code "69") (name "Net-(K10B-S)") (class "Default")
      (node (ref "K10") (pin "4") (pinfunction "S_4") (pintype "passive"))
      (node (ref "X11") (pin "3") (pinfunction "S_3") (pintype "passive"))
    )
    (net (code "70") (name "Net-(K11A--)") (class "Default")
      (node (ref "D11") (pin "A") (pinfunction "A_A") (pintype "passive"))
      (node (ref "K11") (pin "8") (pinfunction "-_8") (pintype "passive"))
      (node (ref "T11") (pin "1") (pinfunction "C_1") (pintype "passive"))
    )
    (net (code "71") (name "Net-(K11B-O)") (class "Default")
      (node (ref "K11") (pin "2") (pinfunction "O_2") (pintype "passive"))
      (node (ref "X12") (pin "1") (pinfunction "S_1") (pintype "passive"))
    )
    (net (code "72") (name "Net-(K11B-P)") (class "Default")
      (node (ref "K11") (pin "3") (pinfunction "P_3") (pintype "passive"))
      (node (ref "X12") (pin "2") (pinfunction "S_2") (pintype "passive"))
    )
    (net (code "73") (name "Net-(K11B-S)") (class "Default")
      (node (ref "K11") (pin "4") (pinfunction "S_4") (pintype "passive"))
      (node (ref "X12") (pin "3") (pinfunction "S_3") (pintype "passive"))
    )
    (net (code "74") (name "Net-(K12A--)") (class "Default")
      (node (ref "D12") (pin "A") (pinfunction "A_A") (pintype "passive"))
      (node (ref "K12") (pin "8") (pinfunction "-_8") (pintype "passive"))
      (node (ref "T12") (pin "1") (pinfunction "C_1") (pintype "passive"))
    )
    (net (code "75") (name "Net-(K12B-O)") (class "Default")
      (node (ref "K12") (pin "2") (pinfunction "O_2") (pintype "passive"))
      (node (ref "X13") (pin "1") (pinfunction "S_1") (pintype "passive"))
    )
    (net (code "76") (name "Net-(K12B-P)") (class "Default")
      (node (ref "K12") (pin "3") (pinfunction "P_3") (pintype "passive"))
      (node (ref "X13") (pin "2") (pinfunction "S_2") (pintype "passive"))
    )
    (net (code "77") (name "Net-(K12B-S)") (class "Default")
      (node (ref "K12") (pin "4") (pinfunction "S_4") (pintype "passive"))
      (node (ref "X13") (pin "3") (pinfunction "S_3") (pintype "passive"))
    )
    (net (code "78") (name "Net-(K13A--)") (class "Default")
      (node (ref "D13") (pin "A") (pinfunction "A_A") (pintype "passive"))
      (node (ref "K13") (pin "8") (pinfunction "-_8") (pintype "passive"))
      (node (ref "T13") (pin "1") (pinfunction "C_1") (pintype "passive"))
    )
    (net (code "79") (name "Net-(K13B-O)") (class "Default")
      (node (ref "K13") (pin "2") (pinfunction "O_2") (pintype "passive"))
      (node (ref "X14") (pin "1") (pinfunction "S_1") (pintype "passive"))
    )
    (net (code "80") (name "Net-(K13B-P)") (class "Default")
      (node (ref "K13") (pin "3") (pinfunction "P_3") (pintype "passive"))
      (node (ref "X14") (pin "2") (pinfunction "S_2") (pintype "passive"))
    )
    (net (code "81") (name "Net-(K13B-S)") (class "Default")
      (node (ref "K13") (pin "4") (pinfunction "S_4") (pintype "passive"))
      (node (ref "X14") (pin "3") (pinfunction "S_3") (pintype "passive"))
    )
    (net (code "82") (name "Net-(K14A--)") (class "Default")
      (node (ref "D14") (pin "A") (pinfunction "A_A") (pintype "passive"))
      (node (ref "K14") (pin "8") (pinfunction "-_8") (pintype "passive"))
      (node (ref "T14") (pin "1") (pinfunction "C_1") (pintype "passive"))
    )
    (net (code "83") (name "Net-(K14B-O)") (class "Default")
      (node (ref "K14") (pin "2") (pinfunction "O_2") (pintype "passive"))
      (node (ref "X15") (pin "1") (pinfunction "S_1") (pintype "passive"))
    )
    (net (code "84") (name "Net-(K14B-P)") (class "Default")
      (node (ref "K14") (pin "3") (pinfunction "P_3") (pintype "passive"))
      (node (ref "X15") (pin "2") (pinfunction "S_2") (pintype "passive"))
    )
    (net (code "85") (name "Net-(K14B-S)") (class "Default")
      (node (ref "K14") (pin "4") (pinfunction "S_4") (pintype "passive"))
      (node (ref "X15") (pin "3") (pinfunction "S_3") (pintype "passive"))
    )
    (net (code "86") (name "Net-(K15A--)") (class "Default")
      (node (ref "D15") (pin "A") (pinfunction "A_A") (pintype "passive"))
      (node (ref "K15") (pin "8") (pinfunction "-_8") (pintype "passive"))
      (node (ref "T15") (pin "1") (pinfunction "C_1") (pintype "passive"))
    )
    (net (code "87") (name "Net-(K15B-O)") (class "Default")
      (node (ref "K15") (pin "2") (pinfunction "O_2") (pintype "passive"))
      (node (ref "X16") (pin "1") (pinfunction "S_1") (pintype "passive"))
    )
    (net (code "88") (name "Net-(K15B-P)") (class "Default")
      (node (ref "K15") (pin "3") (pinfunction "P_3") (pintype "passive"))
      (node (ref "X16") (pin "2") (pinfunction "S_2") (pintype "passive"))
    )
    (net (code "89") (name "Net-(K15B-S)") (class "Default")
      (node (ref "K15") (pin "4") (pinfunction "S_4") (pintype "passive"))
      (node (ref "X16") (pin "3") (pinfunction "S_3") (pintype "passive"))
    )
    (net (code "90") (name "Net-(K16A--)") (class "Default")
      (node (ref "D17") (pin "A") (pinfunction "A_A") (pintype "passive"))
      (node (ref "K16") (pin "8") (pinfunction "-_8") (pintype "passive"))
      (node (ref "T17") (pin "1") (pinfunction "C_1") (pintype "passive"))
    )
    (net (code "91") (name "Net-(K16B-O)") (class "Default")
      (node (ref "K16") (pin "2") (pinfunction "O_2") (pintype "passive"))
      (node (ref "X1") (pin "1") (pinfunction "S_1") (pintype "passive"))
    )
    (net (code "92") (name "Net-(K16B-P)") (class "Default")
      (node (ref "K16") (pin "3") (pinfunction "P_3") (pintype "passive"))
      (node (ref "X1") (pin "2") (pinfunction "S_2") (pintype "passive"))
    )
    (net (code "93") (name "Net-(K16B-S)") (class "Default")
      (node (ref "K16") (pin "4") (pinfunction "S_4") (pintype "passive"))
      (node (ref "X1") (pin "3") (pinfunction "S_3") (pintype "passive"))
    )
    (net (code "94") (name "Net-(T1-B)") (class "Default")
      (node (ref "R2") (pin "2") (pinfunction "2_2") (pintype "passive"))
      (node (ref "T1") (pin "3") (pinfunction "B_3") (pintype "passive"))
    )
    (net (code "95") (name "Net-(T2-B)") (class "Default")
      (node (ref "R3") (pin "2") (pinfunction "2_2") (pintype "passive"))
      (node (ref "T2") (pin "3") (pinfunction "B_3") (pintype "passive"))
    )
    (net (code "96") (name "Net-(T3-B)") (class "Default")
      (node (ref "R4") (pin "2") (pinfunction "2_2") (pintype "passive"))
      (node (ref "T3") (pin "3") (pinfunction "B_3") (pintype "passive"))
    )
    (net (code "97") (name "Net-(T4-B)") (class "Default")
      (node (ref "R5") (pin "2") (pinfunction "2_2") (pintype "passive"))
      (node (ref "T4") (pin "3") (pinfunction "B_3") (pintype "passive"))
    )
    (net (code "98") (name "Net-(T5-B)") (class "Default")
      (node (ref "R6") (pin "2") (pinfunction "2_2") (pintype "passive"))
      (node (ref "T5") (pin "3") (pinfunction "B_3") (pintype "passive"))
    )
    (net (code "99") (name "Net-(T6-B)") (class "Default")
      (node (ref "R7") (pin "2") (pinfunction "2_2") (pintype "passive"))
      (node (ref "T6") (pin "3") (pinfunction "B_3") (pintype "passive"))
    )
    (net (code "100") (name "Net-(T7-B)") (class "Default")
      (node (ref "R8") (pin "2") (pinfunction "2_2") (pintype "passive"))
      (node (ref "T7") (pin "3") (pinfunction "B_3") (pintype "passive"))
    )
    (net (code "101") (name "Net-(T8-B)") (class "Default")
      (node (ref "R9") (pin "2") (pinfunction "2_2") (pintype "passive"))
      (node (ref "T8") (pin "3") (pinfunction "B_3") (pintype "passive"))
    )
    (net (code "102") (name "Net-(T9-B)") (class "Default")
      (node (ref "R10") (pin "2") (pinfunction "2_2") (pintype "passive"))
      (node (ref "T9") (pin "3") (pinfunction "B_3") (pintype "passive"))
    )
    (net (code "103") (name "Net-(T10-B)") (class "Default")
      (node (ref "R11") (pin "2") (pinfunction "2_2") (pintype "passive"))
      (node (ref "T10") (pin "3") (pinfunction "B_3") (pintype "passive"))
    )
    (net (code "104") (name "Net-(T11-B)") (class "Default")
      (node (ref "R12") (pin "2") (pinfunction "2_2") (pintype "passive"))
      (node (ref "T11") (pin "3") (pinfunction "B_3") (pintype "passive"))
    )
    (net (code "105") (name "Net-(T12-B)") (class "Default")
      (node (ref "R13") (pin "2") (pinfunction "2_2") (pintype "passive"))
      (node (ref "T12") (pin "3") (pinfunction "B_3") (pintype "passive"))
    )
    (net (code "106") (name "Net-(T13-B)") (class "Default")
      (node (ref "R14") (pin "2") (pinfunction "2_2") (pintype "passive"))
      (node (ref "T13") (pin "3") (pinfunction "B_3") (pintype "passive"))
    )
    (net (code "107") (name "Net-(T14-B)") (class "Default")
      (node (ref "R15") (pin "2") (pinfunction "2_2") (pintype "passive"))
      (node (ref "T14") (pin "3") (pinfunction "B_3") (pintype "passive"))
    )
    (net (code "108") (name "Net-(T15-B)") (class "Default")
      (node (ref "R16") (pin "2") (pinfunction "2_2") (pintype "passive"))
      (node (ref "T15") (pin "3") (pinfunction "B_3") (pintype "passive"))
    )
    (net (code "109") (name "Net-(T17-B)") (class "Default")
      (node (ref "R1") (pin "2") (pinfunction "2_2") (pintype "passive"))
      (node (ref "T17") (pin "3") (pinfunction "B_3") (pintype "passive"))
    )
    (net (code "110") (name "unconnected-(K1C-O-Pad7)") (class "Default")
      (node (ref "K1") (pin "7") (pinfunction "O_7") (pintype "passive"))
    )
    (net (code "111") (name "unconnected-(K1C-P-Pad6)") (class "Default")
      (node (ref "K1") (pin "6") (pinfunction "P_6") (pintype "passive"))
    )
    (net (code "112") (name "unconnected-(K1C-S-Pad5)") (class "Default")
      (node (ref "K1") (pin "5") (pinfunction "S_5") (pintype "passive"))
    )
    (net (code "113") (name "unconnected-(K2C-O-Pad7)") (class "Default")
      (node (ref "K2") (pin "7") (pinfunction "O_7") (pintype "passive"))
    )
    (net (code "114") (name "unconnected-(K2C-P-Pad6)") (class "Default")
      (node (ref "K2") (pin "6") (pinfunction "P_6") (pintype "passive"))
    )
    (net (code "115") (name "unconnected-(K2C-S-Pad5)") (class "Default")
      (node (ref "K2") (pin "5") (pinfunction "S_5") (pintype "passive"))
    )
    (net (code "116") (name "unconnected-(K3C-O-Pad7)") (class "Default")
      (node (ref "K3") (pin "7") (pinfunction "O_7") (pintype "passive"))
    )
    (net (code "117") (name "unconnected-(K3C-P-Pad6)") (class "Default")
      (node (ref "K3") (pin "6") (pinfunction "P_6") (pintype "passive"))
    )
    (net (code "118") (name "unconnected-(K3C-S-Pad5)") (class "Default")
      (node (ref "K3") (pin "5") (pinfunction "S_5") (pintype "passive"))
    )
    (net (code "119") (name "unconnected-(K4C-O-Pad7)") (class "Default")
      (node (ref "K4") (pin "7") (pinfunction "O_7") (pintype "passive"))
    )
    (net (code "120") (name "unconnected-(K4C-P-Pad6)") (class "Default")
      (node (ref "K4") (pin "6") (pinfunction "P_6") (pintype "passive"))
    )
    (net (code "121") (name "unconnected-(K4C-S-Pad5)") (class "Default")
      (node (ref "K4") (pin "5") (pinfunction "S_5") (pintype "passive"))
    )
    (net (code "122") (name "unconnected-(K5C-O-Pad7)") (class "Default")
      (node (ref "K5") (pin "7") (pinfunction "O_7") (pintype "passive"))
    )
    (net (code "123") (name "unconnected-(K5C-P-Pad6)") (class "Default")
      (node (ref "K5") (pin "6") (pinfunction "P_6") (pintype "passive"))
    )
    (net (code "124") (name "unconnected-(K5C-S-Pad5)") (class "Default")
      (node (ref "K5") (pin "5") (pinfunction "S_5") (pintype "passive"))
    )
    (net (code "125") (name "unconnected-(K6C-O-Pad7)") (class "Default")
      (node (ref "K6") (pin "7") (pinfunction "O_7") (pintype "passive"))
    )
    (net (code "126") (name "unconnected-(K6C-P-Pad6)") (class "Default")
      (node (ref "K6") (pin "6") (pinfunction "P_6") (pintype "passive"))
    )
    (net (code "127") (name "unconnected-(K6C-S-Pad5)") (class "Default")
      (node (ref "K6") (pin "5") (pinfunction "S_5") (pintype "passive"))
    )
    (net (code "128") (name "unconnected-(K7C-O-Pad7)") (class "Default")
      (node (ref "K7") (pin "7") (pinfunction "O_7") (pintype "passive"))
    )
    (net (code "129") (name "unconnected-(K7C-P-Pad6)") (class "Default")
      (node (ref "K7") (pin "6") (pinfunction "P_6") (pintype "passive"))
    )
    (net (code "130") (name "unconnected-(K7C-S-Pad5)") (class "Default")
      (node (ref "K7") (pin "5") (pinfunction "S_5") (pintype "passive"))
    )
    (net (code "131") (name "unconnected-(K8C-O-Pad7)") (class "Default")
      (node (ref "K8") (pin "7") (pinfunction "O_7") (pintype "passive"))
    )
    (net (code "132") (name "unconnected-(K8C-P-Pad6)") (class "Default")
      (node (ref "K8") (pin "6") (pinfunction "P_6") (pintype "passive"))
    )
    (net (code "133") (name "unconnected-(K8C-S-Pad5)") (class "Default")
      (node (ref "K8") (pin "5") (pinfunction "S_5") (pintype "passive"))
    )
    (net (code "134") (name "unconnected-(K9C-O-Pad7)") (class "Default")
      (node (ref "K9") (pin "7") (pinfunction "O_7") (pintype "passive"))
    )
    (net (code "135") (name "unconnected-(K9C-P-Pad6)") (class "Default")
      (node (ref "K9") (pin "6") (pinfunction "P_6") (pintype "passive"))
    )
    (net (code "136") (name "unconnected-(K9C-S-Pad5)") (class "Default")
      (node (ref "K9") (pin "5") (pinfunction "S_5") (pintype "passive"))
    )
    (net (code "137") (name "unconnected-(K10C-O-Pad7)") (class "Default")
      (node (ref "K10") (pin "7") (pinfunction "O_7") (pintype "passive"))
    )
    (net (code "138") (name "unconnected-(K10C-P-Pad6)") (class "Default")
      (node (ref "K10") (pin "6") (pinfunction "P_6") (pintype "passive"))
    )
    (net (code "139") (name "unconnected-(K10C-S-Pad5)") (class "Default")
      (node (ref "K10") (pin "5") (pinfunction "S_5") (pintype "passive"))
    )
    (net (code "140") (name "unconnected-(K11C-O-Pad7)") (class "Default")
      (node (ref "K11") (pin "7") (pinfunction "O_7") (pintype "passive"))
    )
    (net (code "141") (name "unconnected-(K11C-P-Pad6)") (class "Default")
      (node (ref "K11") (pin "6") (pinfunction "P_6") (pintype "passive"))
    )
    (net (code "142") (name "unconnected-(K11C-S-Pad5)") (class "Default")
      (node (ref "K11") (pin "5") (pinfunction "S_5") (pintype "passive"))
    )
    (net (code "143") (name "unconnected-(K12C-O-Pad7)") (class "Default")
      (node (ref "K12") (pin "7") (pinfunction "O_7") (pintype "passive"))
    )
    (net (code "144") (name "unconnected-(K12C-P-Pad6)") (class "Default")
      (node (ref "K12") (pin "6") (pinfunction "P_6") (pintype "passive"))
    )
    (net (code "145") (name "unconnected-(K12C-S-Pad5)") (class "Default")
      (node (ref "K12") (pin "5") (pinfunction "S_5") (pintype "passive"))
    )
    (net (code "146") (name "unconnected-(K13C-O-Pad7)") (class "Default")
      (node (ref "K13") (pin "7") (pinfunction "O_7") (pintype "passive"))
    )
    (net (code "147") (name "unconnected-(K13C-P-Pad6)") (class "Default")
      (node (ref "K13") (pin "6") (pinfunction "P_6") (pintype "passive"))
    )
    (net (code "148") (name "unconnected-(K13C-S-Pad5)") (class "Default")
      (node (ref "K13") (pin "5") (pinfunction "S_5") (pintype "passive"))
    )
    (net (code "149") (name "unconnected-(K14C-O-Pad7)") (class "Default")
      (node (ref "K14") (pin "7") (pinfunction "O_7") (pintype "passive"))
    )
    (net (code "150") (name "unconnected-(K14C-P-Pad6)") (class "Default")
      (node (ref "K14") (pin "6") (pinfunction "P_6") (pintype "passive"))
    )
    (net (code "151") (name "unconnected-(K14C-S-Pad5)") (class "Default")
      (node (ref "K14") (pin "5") (pinfunction "S_5") (pintype "passive"))
    )
    (net (code "152") (name "unconnected-(K15C-O-Pad7)") (class "Default")
      (node (ref "K15") (pin "7") (pinfunction "O_7") (pintype "passive"))
    )
    (net (code "153") (name "unconnected-(K15C-P-Pad6)") (class "Default")
      (node (ref "K15") (pin "6") (pinfunction "P_6") (pintype "passive"))
    )
    (net (code "154") (name "unconnected-(K15C-S-Pad5)") (class "Default")
      (node (ref "K15") (pin "5") (pinfunction "S_5") (pintype "passive"))
    )
    (net (code "155") (name "unconnected-(K16C-O-Pad7)") (class "Default")
      (node (ref "K16") (pin "7") (pinfunction "O_7") (pintype "passive"))
    )
    (net (code "156") (name "unconnected-(K16C-P-Pad6)") (class "Default")
      (node (ref "K16") (pin "6") (pinfunction "P_6") (pintype "passive"))
    )
    (net (code "157") (name "unconnected-(K16C-S-Pad5)") (class "Default")
      (node (ref "K16") (pin "5") (pinfunction "S_5") (pintype "passive"))
    )
  )
)
